# USB.net
KiCad netlist of a schematic drawn in Altium Designer
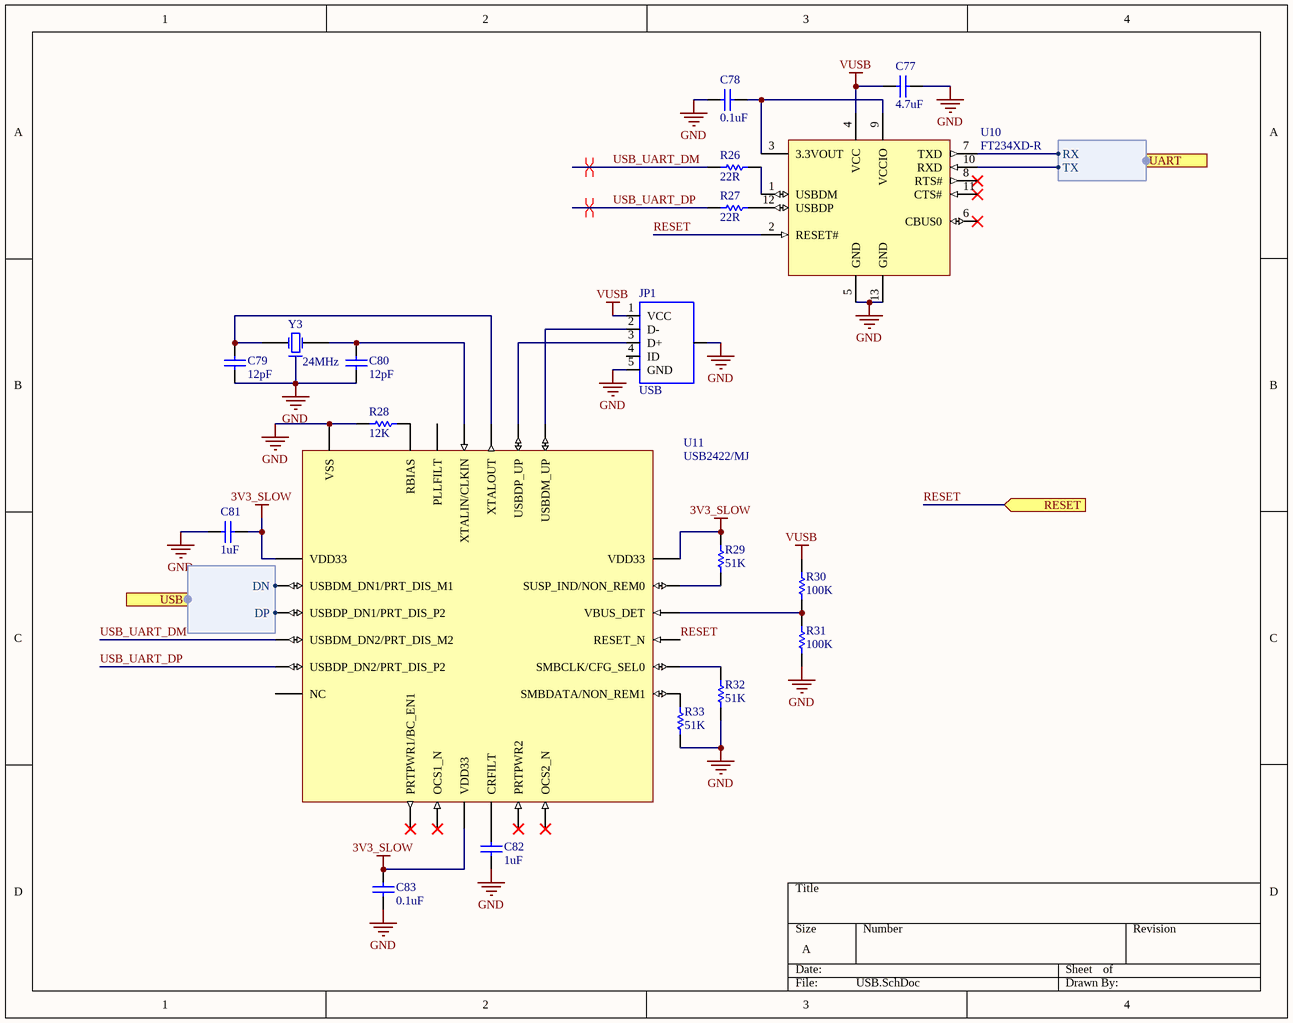
[diagram p0: USB.SchDoc]

(export (version "E")
  (design (tool "Eeschema 10.0.6"))
  (components
    (comp (ref "C77")
      (value "4.7uF")
      (footprint "C0402[1005X55]")
      (description "4.7uF 6.3V 20% 0402 (1005 Metric)")
      (fields (field (name "PARTNUMBER") "GRM155R60J475ME47D") (field (name "MANUFACTURER") "Murata"))
      (libsource (lib "Capacitors") (part "CAP_4.7uF_6.3V_0402_20%"))
    )
    (comp (ref "C78")
      (value "0.1uF")
      (footprint "C0402[1005X55]")
      (description "0.1uF 6.3V 10% 0402 (1005 Metric)")
      (fields (field (name "PARTNUMBER") "GRM155R70J104KA01D") (field (name "MANUFACTURER") "Murata"))
      (libsource (lib "Capacitors") (part "CAP_0.1uF_6.3V_0402_10%"))
    )
    (comp (ref "C79")
      (value "12pF")
      (footprint "C0402[1005X55]")
      (description "12pF 50V 5% 0402 (1005 Metric)")
      (fields (field (name "PARTNUMBER") "GRM1555C1H120JA01D") (field (name "MANUFACTURER") "Murata"))
      (libsource (lib "Capacitors") (part "CAP_12pF_50V_0402_5%"))
    )
    (comp (ref "C80")
      (value "12pF")
      (footprint "C0402[1005X55]")
      (description "12pF 50V 5% 0402 (1005 Metric)")
      (fields (field (name "PARTNUMBER") "GRM1555C1H120JA01D") (field (name "MANUFACTURER") "Murata"))
      (libsource (lib "Capacitors") (part "CAP_12pF_50V_0402_5%"))
    )
    (comp (ref "C81")
      (value "1uF")
      (footprint "C0402[1005X55]")
      (description "1uF 6.3V 10% 0402 (1005 Metric)")
      (fields (field (name "PARTNUMBER") "GRM155R70J105KA12D") (field (name "MANUFACTURER") "Murata"))
      (libsource (lib "Capacitors") (part "CAP_1uF_6.3V_0402_10%"))
    )
    (comp (ref "C82")
      (value "1uF")
      (footprint "C0402[1005X55]")
      (description "1uF 6.3V 10% 0402 (1005 Metric)")
      (fields (field (name "PARTNUMBER") "GRM155R70J105KA12D") (field (name "MANUFACTURER") "Murata"))
      (libsource (lib "Capacitors") (part "CAP_1uF_6.3V_0402_10%"))
    )
    (comp (ref "C83")
      (value "0.1uF")
      (footprint "C0402[1005X55]")
      (description "0.1uF 6.3V 10% 0402 (1005 Metric)")
      (fields (field (name "PARTNUMBER") "GRM155R70J104KA01D") (field (name "MANUFACTURER") "Murata"))
      (libsource (lib "Capacitors") (part "CAP_0.1uF_6.3V_0402_10%"))
    )
    (comp (ref "JP1")
      (value "USB")
      (footprint "USB-MICROB")
      (fields (field (name "PARTNUMBER") "10118192-0001LF") (field (name "MANUFACTURER") "Amphenol FCI"))
      (libsource (lib "Connectors") (part "USB_MICROB_SMT"))
    )
    (comp (ref "R26")
      (value "22R")
      (footprint "R0402[1005]")
      (description "22R 0.063W 1% 0402 (1005 Metric)")
      (fields (field (name "MANUFACTURER") "KOA Speer") (field (name "PARTNUMBER") "RK73H1ETTP22R0F"))
      (libsource (lib "Resistors") (part "RES_22R_0402_1%"))
    )
    (comp (ref "R27")
      (value "22R")
      (footprint "R0402[1005]")
      (description "22R 0.063W 1% 0402 (1005 Metric)")
      (fields (field (name "MANUFACTURER") "KOA Speer") (field (name "PARTNUMBER") "RK73H1ETTP22R0F"))
      (libsource (lib "Resistors") (part "RES_22R_0402_1%"))
    )
    (comp (ref "R28")
      (value "12K")
      (footprint "R0402[1005]")
      (description "12K 0.063W 1% 0402 (1005 Metric)")
      (fields (field (name "MANUFACTURER") "KOA Speer") (field (name "PARTNUMBER") "RK73H1ETTP1202F"))
      (libsource (lib "Resistors") (part "RES_12K_0402_1%"))
    )
    (comp (ref "R29")
      (value "51K")
      (footprint "R0402[1005]")
      (description "51K 0.063W 1% 0402 (1005 Metric)")
      (fields (field (name "MANUFACTURER") "KOA Speer") (field (name "PARTNUMBER") "RK73H1ETTP5102F"))
      (libsource (lib "Resistors") (part "RES_51K_0402_1%"))
    )
    (comp (ref "R30")
      (value "100K")
      (footprint "R0402[1005]")
      (description "100K 0.063W 1% 0402 (1005 Metric)")
      (fields (field (name "MANUFACTURER") "KOA Speer") (field (name "PARTNUMBER") "RK73H1ETTP1003F"))
      (libsource (lib "Resistors") (part "RES_100K_0402_1%"))
    )
    (comp (ref "R31")
      (value "100K")
      (footprint "R0402[1005]")
      (description "100K 0.063W 1% 0402 (1005 Metric)")
      (fields (field (name "MANUFACTURER") "KOA Speer") (field (name "PARTNUMBER") "RK73H1ETTP1003F"))
      (libsource (lib "Resistors") (part "RES_100K_0402_1%"))
    )
    (comp (ref "R32")
      (value "51K")
      (footprint "R0402[1005]")
      (description "51K 0.063W 1% 0402 (1005 Metric)")
      (fields (field (name "MANUFACTURER") "KOA Speer") (field (name "PARTNUMBER") "RK73H1ETTP5102F"))
      (libsource (lib "Resistors") (part "RES_51K_0402_1%"))
    )
    (comp (ref "R33")
      (value "51K")
      (footprint "R0402[1005]")
      (description "51K 0.063W 1% 0402 (1005 Metric)")
      (fields (field (name "MANUFACTURER") "KOA Speer") (field (name "PARTNUMBER") "RK73H1ETTP5102F"))
      (libsource (lib "Resistors") (part "RES_51K_0402_1%"))
    )
    (comp (ref "U10")
      (value "FT234XD-R")
      (footprint "DFN-12")
      (description "USB Interface IC USB to Serial UART Interface")
      (fields (field (name "MANUFACTURER") "FTDI"))
      (libsource (lib "ICs") (part "FT234XD-R"))
    )
    (comp (ref "U11")
      (value "USB2422/MJ")
      (footprint "QFN-24 (4x4MM)")
      (description "USB Hub IC 2-Port")
      (fields (field (name "MANUFACTURER") "Microchip"))
      (libsource (lib "ICs-USBInterface") (part "USB2422/MJ"))
    )
    (comp (ref "Y3")
      (value "24MHz")
      (footprint "CRYSTAL_2.0x1.6")
      (fields (field (name "PARTNUMBER") "FA-128 24.0000MF10Z-W3") (field (name "MANUFACTURER") "EPSON"))
      (libsource (lib "Components") (part "FA-128 24.0000MF10Z-W3"))
    )
  )
  (nets
    (net (code "3") (name "/DN") (class "Default")
      (node (ref "U11") (pin "2") (pinfunction "USBDM_DN1/PRT_DIS_M1_2") (pintype "bidirectional"))
    )
    (net (code "4") (name "/DP") (class "Default")
      (node (ref "U11") (pin "3") (pinfunction "USBDP_DN1/PRT_DIS_P2_3") (pintype "bidirectional"))
    )
    (net (code "5") (name "/RESET") (class "Default")
      (node (ref "U10") (pin "2") (pinfunction "RESET#_2") (pintype "input"))
      (node (ref "U11") (pin "15") (pinfunction "RESET_N_15") (pintype "input"))
    )
    (net (code "6") (name "/RX") (class "Default")
      (node (ref "U10") (pin "7") (pinfunction "TXD_7") (pintype "output"))
    )
    (net (code "7") (name "/TX") (class "Default")
      (node (ref "U10") (pin "10") (pinfunction "RXD_10") (pintype "input"))
    )
    (net (code "8") (name "/USB_UART_DM") (class "Default")
      (node (ref "R26") (pin "1") (pinfunction "1_1") (pintype "passive"))
      (node (ref "U11") (pin "4") (pinfunction "USBDM_DN2/PRT_DIS_M2_4") (pintype "bidirectional"))
    )
    (net (code "9") (name "/USB_UART_DP") (class "Default")
      (node (ref "R27") (pin "1") (pinfunction "1_1") (pintype "passive"))
      (node (ref "U11") (pin "5") (pinfunction "USBDP_DN2/PRT_DIS_P2_5") (pintype "bidirectional"))
    )
    (net (code "12") (name "3V3_SLOW") (class "Default")
      (node (ref "C81") (pin "2") (pinfunction "2_2") (pintype "passive"))
      (node (ref "C83") (pin "2") (pinfunction "2_2") (pintype "passive"))
      (node (ref "R29") (pin "2") (pinfunction "2_2") (pintype "passive"))
      (node (ref "U11") (pin "1") (pinfunction "VDD33_1") (pintype "power_in"))
      (node (ref "U11") (pin "18") (pinfunction "VDD33_18") (pintype "power_in"))
      (node (ref "U11") (pin "9") (pinfunction "VDD33_9") (pintype "power_in"))
    )
    (net (code "13") (name "GND") (class "Default")
      (node (ref "C77") (pin "2") (pinfunction "2_2") (pintype "passive"))
      (node (ref "C78") (pin "2") (pinfunction "2_2") (pintype "passive"))
      (node (ref "C79") (pin "1") (pinfunction "1_1") (pintype "passive"))
      (node (ref "C80") (pin "1") (pinfunction "1_1") (pintype "passive"))
      (node (ref "C81") (pin "1") (pinfunction "1_1") (pintype "passive"))
      (node (ref "C82") (pin "1") (pinfunction "1_1") (pintype "passive"))
      (node (ref "C83") (pin "1") (pinfunction "1_1") (pintype "passive"))
      (node (ref "JP1") (pin "5") (pinfunction "GND_5") (pintype "passive"))
      (node (ref "JP1") (pin "6") (pinfunction "SHIELD_6") (pintype "passive"))
      (node (ref "R28") (pin "1") (pinfunction "1_1") (pintype "passive"))
      (node (ref "R31") (pin "1") (pinfunction "1_1") (pintype "passive"))
      (node (ref "R32") (pin "1") (pinfunction "1_1") (pintype "passive"))
      (node (ref "R33") (pin "1") (pinfunction "1_1") (pintype "passive"))
      (node (ref "U10") (pin "13") (pinfunction "GND_13") (pintype "power_in"))
      (node (ref "U10") (pin "5") (pinfunction "GND_5") (pintype "power_in"))
      (node (ref "U11") (pin "25") (pinfunction "VSS_25") (pintype "power_in"))
      (node (ref "Y3") (pin "2") (pinfunction "2_2") (pintype "passive"))
    )
    (net (code "14") (name "Net-(JP1-D+)") (class "Default")
      (node (ref "JP1") (pin "3") (pinfunction "D+_3") (pintype "passive"))
      (node (ref "U11") (pin "20") (pinfunction "USBDP_UP_20") (pintype "bidirectional"))
    )
    (net (code "15") (name "Net-(JP1-D-)") (class "Default")
      (node (ref "JP1") (pin "2") (pinfunction "D-_2") (pintype "passive"))
      (node (ref "U11") (pin "19") (pinfunction "USBDM_UP_19") (pintype "bidirectional"))
    )
    (net (code "16") (name "Net-(U10-3.3VOUT)") (class "Default")
      (node (ref "C78") (pin "1") (pinfunction "1_1") (pintype "passive"))
      (node (ref "U10") (pin "3") (pinfunction "3.3VOUT_3") (pintype "power_in"))
      (node (ref "U10") (pin "9") (pinfunction "VCCIO_9") (pintype "power_in"))
    )
    (net (code "17") (name "Net-(U10-USBDM)") (class "Default")
      (node (ref "R26") (pin "2") (pinfunction "2_2") (pintype "passive"))
      (node (ref "U10") (pin "1") (pinfunction "USBDM_1") (pintype "bidirectional"))
    )
    (net (code "18") (name "Net-(U10-USBDP)") (class "Default")
      (node (ref "R27") (pin "2") (pinfunction "2_2") (pintype "passive"))
      (node (ref "U10") (pin "12") (pinfunction "USBDP_12") (pintype "bidirectional"))
    )
    (net (code "19") (name "Net-(U11-CRFILT)") (class "Default")
      (node (ref "C82") (pin "2") (pinfunction "2_2") (pintype "passive"))
      (node (ref "U11") (pin "10") (pinfunction "CRFILT_10") (pintype "passive"))
    )
    (net (code "20") (name "Net-(U11-RBIAS)") (class "Default")
      (node (ref "R28") (pin "2") (pinfunction "2_2") (pintype "passive"))
      (node (ref "U11") (pin "24") (pinfunction "RBIAS_24") (pintype "passive"))
    )
    (net (code "21") (name "Net-(U11-SMBCLK{slash}CFG_SEL0)") (class "Default")
      (node (ref "R32") (pin "2") (pinfunction "2_2") (pintype "passive"))
      (node (ref "U11") (pin "14") (pinfunction "SMBCLK/CFG_SEL0_14") (pintype "bidirectional"))
    )
    (net (code "22") (name "Net-(U11-SMBDATA{slash}NON_REM1)") (class "Default")
      (node (ref "R33") (pin "2") (pinfunction "2_2") (pintype "passive"))
      (node (ref "U11") (pin "13") (pinfunction "SMBDATA/NON_REM1_13") (pintype "bidirectional"))
    )
    (net (code "23") (name "Net-(U11-SUSP_IND{slash}NON_REM0)") (class "Default")
      (node (ref "R29") (pin "1") (pinfunction "1_1") (pintype "passive"))
      (node (ref "U11") (pin "17") (pinfunction "SUSP_IND/NON_REM0_17") (pintype "bidirectional"))
    )
    (net (code "24") (name "Net-(U11-VBUS_DET)") (class "Default")
      (node (ref "R30") (pin "1") (pinfunction "1_1") (pintype "passive"))
      (node (ref "R31") (pin "2") (pinfunction "2_2") (pintype "passive"))
      (node (ref "U11") (pin "16") (pinfunction "VBUS_DET_16") (pintype "input"))
    )
    (net (code "25") (name "Net-(U11-XTALIN{slash}CLKIN)") (class "Default")
      (node (ref "C80") (pin "2") (pinfunction "2_2") (pintype "passive"))
      (node (ref "U11") (pin "22") (pinfunction "XTALIN/CLKIN_22") (pintype "input"))
      (node (ref "Y3") (pin "3") (pinfunction "X2_3") (pintype "passive"))
    )
    (net (code "26") (name "Net-(U11-XTALOUT)") (class "Default")
      (node (ref "C79") (pin "2") (pinfunction "2_2") (pintype "passive"))
      (node (ref "U11") (pin "21") (pinfunction "XTALOUT_21") (pintype "output"))
      (node (ref "Y3") (pin "1") (pinfunction "X1_1") (pintype "passive"))
    )
    (net (code "27") (name "VUSB") (class "Default")
      (node (ref "C77") (pin "1") (pinfunction "1_1") (pintype "passive"))
      (node (ref "JP1") (pin "1") (pinfunction "VCC_1") (pintype "passive"))
      (node (ref "R30") (pin "2") (pinfunction "2_2") (pintype "passive"))
      (node (ref "U10") (pin "4") (pinfunction "VCC_4") (pintype "power_in"))
    )
    (net (code "28") (name "unconnected-(JP1-ID-Pad4)") (class "Default")
      (node (ref "JP1") (pin "4") (pinfunction "ID_4") (pintype "passive"))
    )
    (net (code "29") (name "unconnected-(U10-CBUS0-Pad6)") (class "Default")
      (node (ref "U10") (pin "6") (pinfunction "CBUS0_6") (pintype "bidirectional+no_connect"))
    )
    (net (code "30") (name "unconnected-(U10-CTS#-Pad11)") (class "Default")
      (node (ref "U10") (pin "11") (pinfunction "CTS#_11") (pintype "input+no_connect"))
    )
    (net (code "31") (name "unconnected-(U10-RTS#-Pad8)") (class "Default")
      (node (ref "U10") (pin "8") (pinfunction "RTS#_8") (pintype "output+no_connect"))
    )
    (net (code "32") (name "unconnected-(U11-NC-Pad6)") (class "Default")
      (node (ref "U11") (pin "6") (pinfunction "NC_6") (pintype "passive"))
    )
    (net (code "33") (name "unconnected-(U11-OCS1_N-Pad8)") (class "Default")
      (node (ref "U11") (pin "8") (pinfunction "OCS1_N_8") (pintype "input+no_connect"))
    )
    (net (code "34") (name "unconnected-(U11-OCS2_N-Pad12)") (class "Default")
      (node (ref "U11") (pin "12") (pinfunction "OCS2_N_12") (pintype "input+no_connect"))
    )
    (net (code "35") (name "unconnected-(U11-PLLFILT-Pad23)") (class "Default")
      (node (ref "U11") (pin "23") (pinfunction "PLLFILT_23") (pintype "passive"))
    )
    (net (code "36") (name "unconnected-(U11-PRTPWR1{slash}BC_EN1-Pad7)") (class "Default")
      (node (ref "U11") (pin "7") (pinfunction "PRTPWR1/BC_EN1_7") (pintype "output+no_connect"))
    )
    (net (code "37") (name "unconnected-(U11-PRTPWR2-Pad11)") (class "Default")
      (node (ref "U11") (pin "11") (pinfunction "PRTPWR2_11") (pintype "input+no_connect"))
    )
  )
)
